# Promless_Power.net
KiCad netlist of a schematic drawn in Altium Designer
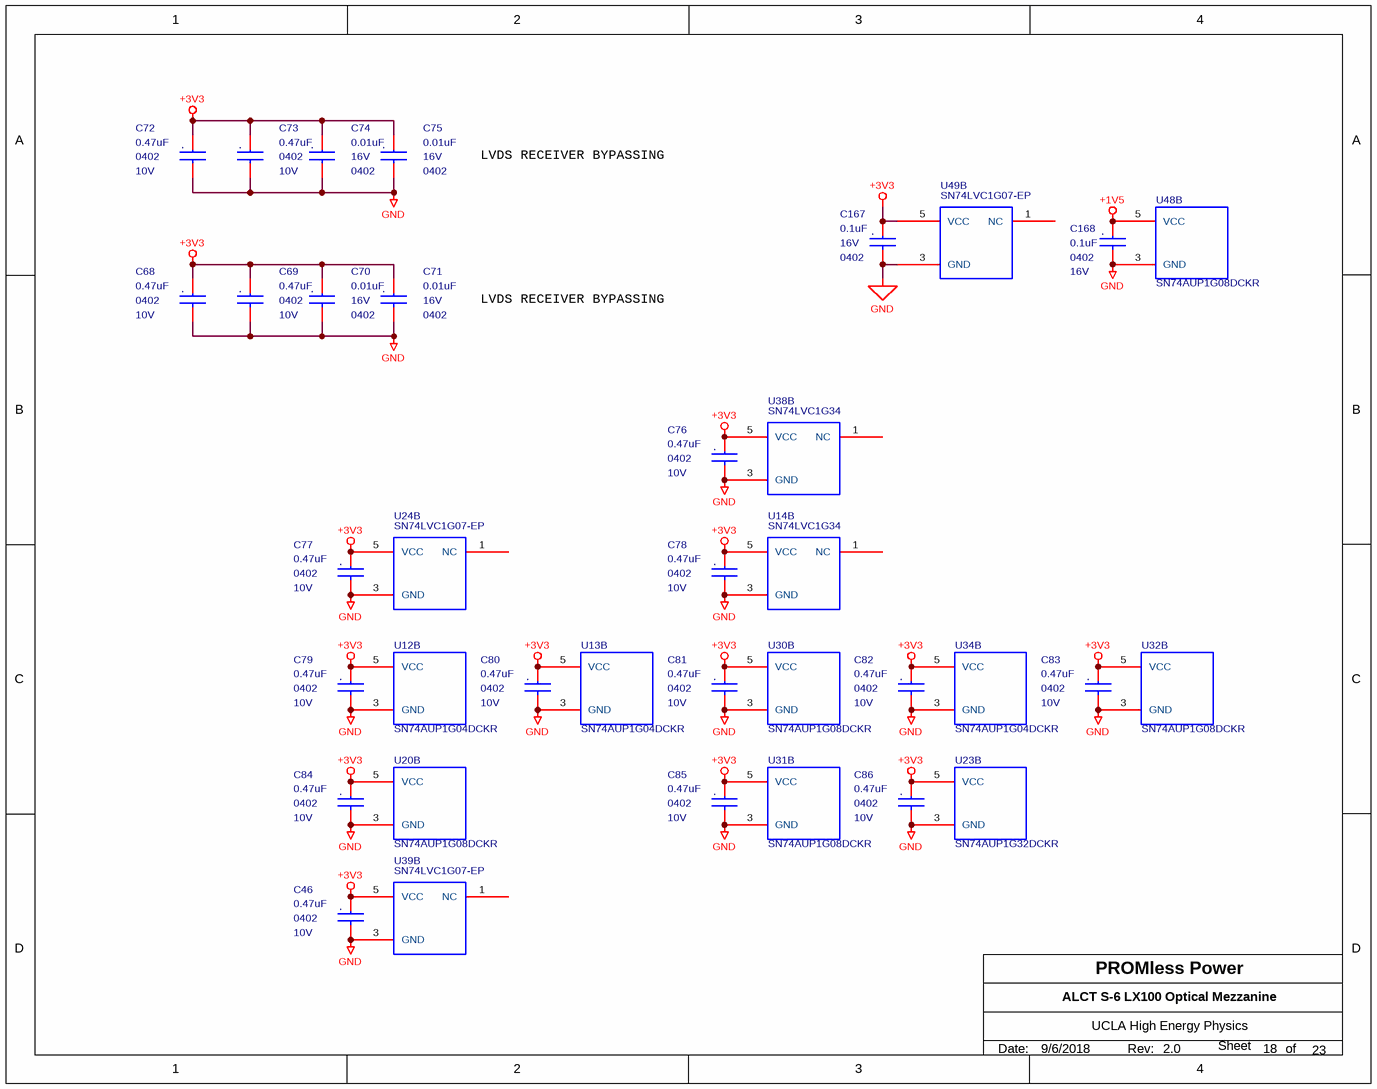
[diagram p0: Promless_Power.SchDoc]

(export (version "E")
  (design (tool "Eeschema 10.0.6"))
  (components
    (comp (ref "C46")
      (value "0.47uF")
      (footprint "MC_S6/SM/C_0402_IPC")
      (description "CAP CER 0.47UF 10V X5R 0402")
      (fields
        (field (name "MANUFACTURER") "Murata Electronics North America")
        (field (name "MANUFACTURER PART NUMBER") "GRM155R61A474KE15D")
        (field (name "VOLTAGE - RATED") "10V")
        (field (name "PACKAGE") "0402")
      )
      (libsource (lib "ALCT_MEZ_SPARTAN6_Library") (part "GRM155R61A474KE15D"))
    )
    (comp (ref "C68")
      (value "0.47uF")
      (footprint "MC_S6/SM/C_0402_IPC")
      (description "CAP CER 0.47UF 10V X5R 0402")
      (fields
        (field (name "MANUFACTURER") "Murata Electronics North America")
        (field (name "MANUFACTURER PART NUMBER") "GRM155R61A474KE15D")
        (field (name "VOLTAGE - RATED") "10V")
        (field (name "PACKAGE") "0402")
      )
      (libsource (lib "ALCT_MEZ_SPARTAN6_Library") (part "GRM155R61A474KE15D"))
    )
    (comp (ref "C69")
      (value "0.47uF")
      (footprint "MC_S6/SM/C_0402_IPC")
      (description "CAP CER 0.47UF 10V X5R 0402")
      (fields
        (field (name "MANUFACTURER") "Murata Electronics North America")
        (field (name "MANUFACTURER PART NUMBER") "GRM155R61A474KE15D")
        (field (name "VOLTAGE - RATED") "10V")
        (field (name "PACKAGE") "0402")
      )
      (libsource (lib "ALCT_MEZ_SPARTAN6_Library") (part "GRM155R61A474KE15D"))
    )
    (comp (ref "C70")
      (value "0.01uF")
      (footprint "MC_S6/SM/C_0402_IPC")
      (description "CAP CER 10nF 16V X7R 0402")
      (fields
        (field (name "MANUFACTURER") "KEMET")
        (field (name "MANUFACTURER PART NUMBER") "C0402C103K4RACTU")
        (field (name "VOLTAGE - RATED") "16V")
        (field (name "PACKAGE") "0402")
      )
      (libsource (lib "ALCT_MEZ_SPARTAN6_Library") (part "C0402C103K4RACTU"))
    )
    (comp (ref "C71")
      (value "0.01uF")
      (footprint "MC_S6/SM/C_0402_IPC")
      (description "CAP CER 10nF 16V X7R 0402")
      (fields
        (field (name "MANUFACTURER") "KEMET")
        (field (name "MANUFACTURER PART NUMBER") "C0402C103K4RACTU")
        (field (name "VOLTAGE - RATED") "16V")
        (field (name "PACKAGE") "0402")
      )
      (libsource (lib "ALCT_MEZ_SPARTAN6_Library") (part "C0402C103K4RACTU"))
    )
    (comp (ref "C72")
      (value "0.47uF")
      (footprint "MC_S6/SM/C_0402_IPC")
      (description "CAP CER 0.47UF 10V X5R 0402")
      (fields
        (field (name "MANUFACTURER") "Murata Electronics North America")
        (field (name "MANUFACTURER PART NUMBER") "GRM155R61A474KE15D")
        (field (name "VOLTAGE - RATED") "10V")
        (field (name "PACKAGE") "0402")
      )
      (libsource (lib "ALCT_MEZ_SPARTAN6_Library") (part "GRM155R61A474KE15D"))
    )
    (comp (ref "C73")
      (value "0.47uF")
      (footprint "MC_S6/SM/C_0402_IPC")
      (description "CAP CER 0.47UF 10V X5R 0402")
      (fields
        (field (name "MANUFACTURER") "Murata Electronics North America")
        (field (name "MANUFACTURER PART NUMBER") "GRM155R61A474KE15D")
        (field (name "VOLTAGE - RATED") "10V")
        (field (name "PACKAGE") "0402")
      )
      (libsource (lib "ALCT_MEZ_SPARTAN6_Library") (part "GRM155R61A474KE15D"))
    )
    (comp (ref "C74")
      (value "0.01uF")
      (footprint "MC_S6/SM/C_0402_IPC")
      (description "CAP CER 10nF 16V X7R 0402")
      (fields
        (field (name "MANUFACTURER") "KEMET")
        (field (name "MANUFACTURER PART NUMBER") "C0402C103K4RACTU")
        (field (name "VOLTAGE - RATED") "16V")
        (field (name "PACKAGE") "0402")
      )
      (libsource (lib "ALCT_MEZ_SPARTAN6_Library") (part "C0402C103K4RACTU"))
    )
    (comp (ref "C75")
      (value "0.01uF")
      (footprint "MC_S6/SM/C_0402_IPC")
      (description "CAP CER 10nF 16V X7R 0402")
      (fields
        (field (name "MANUFACTURER") "KEMET")
        (field (name "MANUFACTURER PART NUMBER") "C0402C103K4RACTU")
        (field (name "VOLTAGE - RATED") "16V")
        (field (name "PACKAGE") "0402")
      )
      (libsource (lib "ALCT_MEZ_SPARTAN6_Library") (part "C0402C103K4RACTU"))
    )
    (comp (ref "C76")
      (value "0.47uF")
      (footprint "MC_S6/SM/C_0402_IPC")
      (description "CAP CER 0.47UF 10V X5R 0402")
      (fields
        (field (name "MANUFACTURER") "Murata Electronics North America")
        (field (name "MANUFACTURER PART NUMBER") "GRM155R61A474KE15D")
        (field (name "VOLTAGE - RATED") "10V")
        (field (name "PACKAGE") "0402")
      )
      (libsource (lib "ALCT_MEZ_SPARTAN6_Library") (part "GRM155R61A474KE15D"))
    )
    (comp (ref "C77")
      (value "0.47uF")
      (footprint "MC_S6/SM/C_0402_IPC")
      (description "CAP CER 0.47UF 10V X5R 0402")
      (fields
        (field (name "MANUFACTURER") "Murata Electronics North America")
        (field (name "MANUFACTURER PART NUMBER") "GRM155R61A474KE15D")
        (field (name "VOLTAGE - RATED") "10V")
        (field (name "PACKAGE") "0402")
      )
      (libsource (lib "ALCT_MEZ_SPARTAN6_Library") (part "GRM155R61A474KE15D"))
    )
    (comp (ref "C78")
      (value "0.47uF")
      (footprint "MC_S6/SM/C_0402_IPC")
      (description "CAP CER 0.47UF 10V X5R 0402")
      (fields
        (field (name "MANUFACTURER") "Murata Electronics North America")
        (field (name "MANUFACTURER PART NUMBER") "GRM155R61A474KE15D")
        (field (name "VOLTAGE - RATED") "10V")
        (field (name "PACKAGE") "0402")
      )
      (libsource (lib "ALCT_MEZ_SPARTAN6_Library") (part "GRM155R61A474KE15D"))
    )
    (comp (ref "C79")
      (value "0.47uF")
      (footprint "MC_S6/SM/C_0402_IPC")
      (description "CAP CER 0.47UF 10V X5R 0402")
      (fields
        (field (name "MANUFACTURER") "Murata Electronics North America")
        (field (name "MANUFACTURER PART NUMBER") "GRM155R61A474KE15D")
        (field (name "VOLTAGE - RATED") "10V")
        (field (name "PACKAGE") "0402")
      )
      (libsource (lib "ALCT_MEZ_SPARTAN6_Library") (part "GRM155R61A474KE15D"))
    )
    (comp (ref "C80")
      (value "0.47uF")
      (footprint "MC_S6/SM/C_0402_IPC")
      (description "CAP CER 0.47UF 10V X5R 0402")
      (fields
        (field (name "MANUFACTURER") "Murata Electronics North America")
        (field (name "MANUFACTURER PART NUMBER") "GRM155R61A474KE15D")
        (field (name "VOLTAGE - RATED") "10V")
        (field (name "PACKAGE") "0402")
      )
      (libsource (lib "ALCT_MEZ_SPARTAN6_Library") (part "GRM155R61A474KE15D"))
    )
    (comp (ref "C81")
      (value "0.47uF")
      (footprint "MC_S6/SM/C_0402_IPC")
      (description "CAP CER 0.47UF 10V X5R 0402")
      (fields
        (field (name "MANUFACTURER") "Murata Electronics North America")
        (field (name "MANUFACTURER PART NUMBER") "GRM155R61A474KE15D")
        (field (name "VOLTAGE - RATED") "10V")
        (field (name "PACKAGE") "0402")
      )
      (libsource (lib "ALCT_MEZ_SPARTAN6_Library") (part "GRM155R61A474KE15D"))
    )
    (comp (ref "C82")
      (value "0.47uF")
      (footprint "MC_S6/SM/C_0402_IPC")
      (description "CAP CER 0.47UF 10V X5R 0402")
      (fields
        (field (name "MANUFACTURER") "Murata Electronics North America")
        (field (name "MANUFACTURER PART NUMBER") "GRM155R61A474KE15D")
        (field (name "VOLTAGE - RATED") "10V")
        (field (name "PACKAGE") "0402")
      )
      (libsource (lib "ALCT_MEZ_SPARTAN6_Library") (part "GRM155R61A474KE15D"))
    )
    (comp (ref "C83")
      (value "0.47uF")
      (footprint "MC_S6/SM/C_0402_IPC")
      (description "CAP CER 0.47UF 10V X5R 0402")
      (fields
        (field (name "MANUFACTURER") "Murata Electronics North America")
        (field (name "MANUFACTURER PART NUMBER") "GRM155R61A474KE15D")
        (field (name "VOLTAGE - RATED") "10V")
        (field (name "PACKAGE") "0402")
      )
      (libsource (lib "ALCT_MEZ_SPARTAN6_Library") (part "GRM155R61A474KE15D"))
    )
    (comp (ref "C84")
      (value "0.47uF")
      (footprint "MC_S6/SM/C_0402_IPC")
      (description "CAP CER 0.47UF 10V X5R 0402")
      (fields
        (field (name "MANUFACTURER") "Murata Electronics North America")
        (field (name "MANUFACTURER PART NUMBER") "GRM155R61A474KE15D")
        (field (name "VOLTAGE - RATED") "10V")
        (field (name "PACKAGE") "0402")
      )
      (libsource (lib "ALCT_MEZ_SPARTAN6_Library") (part "GRM155R61A474KE15D"))
    )
    (comp (ref "C85")
      (value "0.47uF")
      (footprint "MC_S6/SM/C_0402_IPC")
      (description "CAP CER 0.47UF 10V X5R 0402")
      (fields
        (field (name "MANUFACTURER") "Murata Electronics North America")
        (field (name "MANUFACTURER PART NUMBER") "GRM155R61A474KE15D")
        (field (name "VOLTAGE - RATED") "10V")
        (field (name "PACKAGE") "0402")
      )
      (libsource (lib "ALCT_MEZ_SPARTAN6_Library") (part "GRM155R61A474KE15D"))
    )
    (comp (ref "C86")
      (value "0.47uF")
      (footprint "MC_S6/SM/C_0402_IPC")
      (description "CAP CER 0.47UF 10V X5R 0402")
      (fields
        (field (name "MANUFACTURER") "Murata Electronics North America")
        (field (name "MANUFACTURER PART NUMBER") "GRM155R61A474KE15D")
        (field (name "VOLTAGE - RATED") "10V")
        (field (name "PACKAGE") "0402")
      )
      (libsource (lib "ALCT_MEZ_SPARTAN6_Library") (part "GRM155R61A474KE15D"))
    )
    (comp (ref "C167")
      (value "0.1uF")
      (footprint "MC_S6/SM/C_0402_IPC")
      (description "CAP CER 0.1UF 16V X7R 0402")
      (fields
        (field (name "MANUFACTURER") "KEMET")
        (field (name "MANUFACTURER PART NUMBER") "C0402C104K4RACTU")
        (field (name "PACKAGE") "0402")
        (field (name "VOLTAGE - RATED") "16V")
      )
      (libsource (lib "ALCT_MEZ_SPARTAN6_Library") (part "C0402C104K4RACTU"))
    )
    (comp (ref "C168")
      (value "0.1uF")
      (footprint "MC_S6/SM/C_0402_IPC")
      (description "CAP CER 0.1UF 16V X7R 0402")
      (fields
        (field (name "MANUFACTURER") "KEMET")
        (field (name "MANUFACTURER PART NUMBER") "C0402C104K4RACTU")
        (field (name "PACKAGE") "0402")
        (field (name "VOLTAGE - RATED") "16V")
      )
      (libsource (lib "ALCT_MEZ_SPARTAN6_Library") (part "C0402C104K4RACTU"))
    )
    (comp (ref "U12")
      (value "SN74AUP1G04DCKR")
      (footprint "MC_S6/SM/SOT_SC70_DCK5")
      (description "IC INVERTER LP 5TSSOP")
      (fields (field (name "MANUFACTURER") "Texas Instruments"))
      (libsource (lib "ALCT_MEZ_SPARTAN6_Library") (part "SN74AUP1G04DCKR"))
    )
    (comp (ref "U13")
      (value "SN74AUP1G04DCKR")
      (footprint "MC_S6/SM/SOT_SC70_DCK5")
      (description "IC INVERTER LP 5TSSOP")
      (fields (field (name "MANUFACTURER") "Texas Instruments"))
      (libsource (lib "ALCT_MEZ_SPARTAN6_Library") (part "SN74AUP1G04DCKR"))
    )
    (comp (ref "U14")
      (value "SN74LVC1G34")
      (footprint "MC_S6/SM/SOT_553_DRL5")
      (description "IC BUFFER NON-INVERT SOT5")
      (fields
        (field (name "MANUFACTURER") "Texas Instruments")
        (field (name "MANUFACTURER PART NUMBER") "SN74LVC1G34DRLR")
      )
      (libsource (lib "ALCT_MEZ_SPARTAN6_Library") (part "SN74LVC1G34DRLR"))
    )
    (comp (ref "U20")
      (value "SN74AUP1G08DCKR")
      (footprint "MC_S6/SM/SOT_SC70_DCK5")
      (description "IC GATE AND 1CH 2-INP 5-TSSOP")
      (fields
        (field (name "MANUFACTURER") "Texas Instruments")
        (field (name "MANUFACTURER PART NUMBER") "SN74AUP1G08DCKT")
      )
      (libsource (lib "ALCT_MEZ_SPARTAN6_Library") (part "SN74AUP1G08DCKR"))
    )
    (comp (ref "U23")
      (value "SN74AUP1G32DCKR")
      (footprint "MC_S6/SM/SOT_SC70_DCK5")
      (description "IC GATE OR 1CH 2-INP 5-TSSOP")
      (fields
        (field (name "MANUFACTURER") "Texas Instruments")
        (field (name "MANUFACTURER PART NUMBER") "SN74AUP1G32DCKT")
      )
      (libsource (lib "ALCT_MEZ_SPARTAN6_Library") (part "SN74AUP1G32DCKR"))
    )
    (comp (ref "U24")
      (value "SN74LVC1G07-EP")
      (footprint "SOT353-1")
      (description "IC BUFF/DVR NON-INVERT Open Drain SC70-5")
      (fields
        (field (name "MANUFACTURER") "Texas Instruments")
        (field (name "MANUFACTURER PART NUMBER") "SN74LVC1G07MDCKREP")
      )
      (libsource (lib "ALCT_MEZ_SPARTAN6_Library") (part "SN74LVC1G07-EP"))
    )
    (comp (ref "U30")
      (value "SN74AUP1G08DCKR")
      (footprint "MC_S6/SM/SOT_SC70_DCK5")
      (description "IC GATE AND 1CH 2-INP 5-TSSOP")
      (fields
        (field (name "MANUFACTURER") "Texas Instruments")
        (field (name "MANUFACTURER PART NUMBER") "SN74AUP1G08DCKT")
      )
      (libsource (lib "ALCT_MEZ_SPARTAN6_Library") (part "SN74AUP1G08DCKR"))
    )
    (comp (ref "U31")
      (value "SN74AUP1G08DCKR")
      (footprint "MC_S6/SM/SOT_SC70_DCK5")
      (description "IC GATE AND 1CH 2-INP 5-TSSOP")
      (fields
        (field (name "MANUFACTURER") "Texas Instruments")
        (field (name "MANUFACTURER PART NUMBER") "SN74AUP1G08DCKT")
      )
      (libsource (lib "ALCT_MEZ_SPARTAN6_Library") (part "SN74AUP1G08DCKR"))
    )
    (comp (ref "U32")
      (value "SN74AUP1G08DCKR")
      (footprint "MC_S6/SM/SOT_SC70_DCK5")
      (description "IC GATE AND 1CH 2-INP 5-TSSOP")
      (fields
        (field (name "MANUFACTURER") "Texas Instruments")
        (field (name "MANUFACTURER PART NUMBER") "SN74AUP1G08DCKT")
      )
      (libsource (lib "ALCT_MEZ_SPARTAN6_Library") (part "SN74AUP1G08DCKR"))
    )
    (comp (ref "U34")
      (value "SN74AUP1G04DCKR")
      (footprint "MC_S6/SM/SOT_SC70_DCK5")
      (description "IC INVERTER LP 5TSSOP")
      (fields (field (name "MANUFACTURER") "Texas Instruments"))
      (libsource (lib "ALCT_MEZ_SPARTAN6_Library") (part "SN74AUP1G04DCKR"))
    )
    (comp (ref "U38")
      (value "SN74LVC1G34")
      (footprint "MC_S6/SM/SOT_553_DRL5")
      (description "IC BUFFER NON-INVERT SOT5")
      (fields
        (field (name "MANUFACTURER") "Texas Instruments")
        (field (name "MANUFACTURER PART NUMBER") "SN74LVC1G34DRLR")
      )
      (libsource (lib "ALCT_MEZ_SPARTAN6_Library") (part "SN74LVC1G34DRLR"))
    )
    (comp (ref "U39")
      (value "SN74LVC1G07-EP")
      (footprint "SOT353-1")
      (description "IC BUFF/DVR NON-INVERT Open Drain SC70-5")
      (fields
        (field (name "MANUFACTURER") "Texas Instruments")
        (field (name "MANUFACTURER PART NUMBER") "SN74LVC1G07MDCKREP")
      )
      (libsource (lib "ALCT_MEZ_SPARTAN6_Library") (part "SN74LVC1G07-EP"))
    )
    (comp (ref "U48")
      (value "SN74AUP1G08DCKR")
      (footprint "MC_S6/SM/SOT_SC70_DCK5")
      (description "IC GATE AND 1CH 2-INP 5-TSSOP")
      (fields
        (field (name "MANUFACTURER") "Texas Instruments")
        (field (name "MANUFACTURER PART NUMBER") "SN74AUP1G08DCKT")
      )
      (libsource (lib "ALCT_MEZ_SPARTAN6_Library") (part "SN74AUP1G08DCKR"))
    )
    (comp (ref "U49")
      (value "SN74LVC1G07-EP")
      (footprint "SOT353-1")
      (description "IC BUFF/DVR NON-INVERT Open Drain SC70-5")
      (fields
        (field (name "MANUFACTURER") "Texas Instruments")
        (field (name "MANUFACTURER PART NUMBER") "SN74LVC1G07MDCKREP")
      )
      (libsource (lib "ALCT_MEZ_SPARTAN6_Library") (part "SN74LVC1G07-EP"))
    )
  )
  (nets
    (net (code "1") (name "+1V5") (class "Default")
      (node (ref "C168") (pin "1") (pinfunction "1_1") (pintype "passive"))
      (node (ref "U48") (pin "5") (pinfunction "VCC_5") (pintype "power_in"))
    )
    (net (code "2") (name "+3V3") (class "Default")
      (node (ref "C167") (pin "1") (pinfunction "1_1") (pintype "passive"))
      (node (ref "C46") (pin "1") (pinfunction "1_1") (pintype "passive"))
      (node (ref "C68") (pin "1") (pinfunction "1_1") (pintype "passive"))
      (node (ref "C69") (pin "1") (pinfunction "1_1") (pintype "passive"))
      (node (ref "C70") (pin "1") (pinfunction "1_1") (pintype "passive"))
      (node (ref "C71") (pin "1") (pinfunction "1_1") (pintype "passive"))
      (node (ref "C72") (pin "1") (pinfunction "1_1") (pintype "passive"))
      (node (ref "C73") (pin "1") (pinfunction "1_1") (pintype "passive"))
      (node (ref "C74") (pin "1") (pinfunction "1_1") (pintype "passive"))
      (node (ref "C75") (pin "1") (pinfunction "1_1") (pintype "passive"))
      (node (ref "C76") (pin "1") (pinfunction "1_1") (pintype "passive"))
      (node (ref "C77") (pin "1") (pinfunction "1_1") (pintype "passive"))
      (node (ref "C78") (pin "1") (pinfunction "1_1") (pintype "passive"))
      (node (ref "C79") (pin "1") (pinfunction "1_1") (pintype "passive"))
      (node (ref "C80") (pin "1") (pinfunction "1_1") (pintype "passive"))
      (node (ref "C81") (pin "1") (pinfunction "1_1") (pintype "passive"))
      (node (ref "C82") (pin "1") (pinfunction "1_1") (pintype "passive"))
      (node (ref "C83") (pin "1") (pinfunction "1_1") (pintype "passive"))
      (node (ref "C84") (pin "1") (pinfunction "1_1") (pintype "passive"))
      (node (ref "C85") (pin "1") (pinfunction "1_1") (pintype "passive"))
      (node (ref "C86") (pin "1") (pinfunction "1_1") (pintype "passive"))
      (node (ref "U12") (pin "5") (pinfunction "VCC_5") (pintype "power_in"))
      (node (ref "U13") (pin "5") (pinfunction "VCC_5") (pintype "power_in"))
      (node (ref "U14") (pin "5") (pinfunction "VCC_5") (pintype "power_in"))
      (node (ref "U20") (pin "5") (pinfunction "VCC_5") (pintype "power_in"))
      (node (ref "U23") (pin "5") (pinfunction "VCC_5") (pintype "power_in"))
      (node (ref "U24") (pin "5") (pinfunction "VCC_5") (pintype "power_in"))
      (node (ref "U30") (pin "5") (pinfunction "VCC_5") (pintype "power_in"))
      (node (ref "U31") (pin "5") (pinfunction "VCC_5") (pintype "power_in"))
      (node (ref "U32") (pin "5") (pinfunction "VCC_5") (pintype "power_in"))
      (node (ref "U34") (pin "5") (pinfunction "VCC_5") (pintype "power_in"))
      (node (ref "U38") (pin "5") (pinfunction "VCC_5") (pintype "power_in"))
      (node (ref "U39") (pin "5") (pinfunction "VCC_5") (pintype "power_in"))
      (node (ref "U49") (pin "5") (pinfunction "VCC_5") (pintype "power_in"))
    )
    (net (code "3") (name "GND") (class "Default")
      (node (ref "C167") (pin "2") (pinfunction "2_2") (pintype "passive"))
      (node (ref "C168") (pin "2") (pinfunction "2_2") (pintype "passive"))
      (node (ref "C46") (pin "2") (pinfunction "2_2") (pintype "passive"))
      (node (ref "C68") (pin "2") (pinfunction "2_2") (pintype "passive"))
      (node (ref "C69") (pin "2") (pinfunction "2_2") (pintype "passive"))
      (node (ref "C70") (pin "2") (pinfunction "2_2") (pintype "passive"))
      (node (ref "C71") (pin "2") (pinfunction "2_2") (pintype "passive"))
      (node (ref "C72") (pin "2") (pinfunction "2_2") (pintype "passive"))
      (node (ref "C73") (pin "2") (pinfunction "2_2") (pintype "passive"))
      (node (ref "C74") (pin "2") (pinfunction "2_2") (pintype "passive"))
      (node (ref "C75") (pin "2") (pinfunction "2_2") (pintype "passive"))
      (node (ref "C76") (pin "2") (pinfunction "2_2") (pintype "passive"))
      (node (ref "C77") (pin "2") (pinfunction "2_2") (pintype "passive"))
      (node (ref "C78") (pin "2") (pinfunction "2_2") (pintype "passive"))
      (node (ref "C79") (pin "2") (pinfunction "2_2") (pintype "passive"))
      (node (ref "C80") (pin "2") (pinfunction "2_2") (pintype "passive"))
      (node (ref "C81") (pin "2") (pinfunction "2_2") (pintype "passive"))
      (node (ref "C82") (pin "2") (pinfunction "2_2") (pintype "passive"))
      (node (ref "C83") (pin "2") (pinfunction "2_2") (pintype "passive"))
      (node (ref "C84") (pin "2") (pinfunction "2_2") (pintype "passive"))
      (node (ref "C85") (pin "2") (pinfunction "2_2") (pintype "passive"))
      (node (ref "C86") (pin "2") (pinfunction "2_2") (pintype "passive"))
      (node (ref "U12") (pin "3") (pinfunction "GND_3") (pintype "power_in"))
      (node (ref "U13") (pin "3") (pinfunction "GND_3") (pintype "power_in"))
      (node (ref "U14") (pin "3") (pinfunction "GND_3") (pintype "power_in"))
      (node (ref "U20") (pin "3") (pinfunction "GND_3") (pintype "power_in"))
      (node (ref "U23") (pin "3") (pinfunction "GND_3") (pintype "power_in"))
      (node (ref "U24") (pin "3") (pinfunction "GND_3") (pintype "power_in"))
      (node (ref "U30") (pin "3") (pinfunction "GND_3") (pintype "power_in"))
      (node (ref "U31") (pin "3") (pinfunction "GND_3") (pintype "power_in"))
      (node (ref "U32") (pin "3") (pinfunction "GND_3") (pintype "power_in"))
      (node (ref "U34") (pin "3") (pinfunction "GND_3") (pintype "power_in"))
      (node (ref "U38") (pin "3") (pinfunction "GND_3") (pintype "power_in"))
      (node (ref "U39") (pin "3") (pinfunction "GND_3") (pintype "power_in"))
      (node (ref "U48") (pin "3") (pinfunction "GND_3") (pintype "power_in"))
      (node (ref "U49") (pin "3") (pinfunction "GND_3") (pintype "power_in"))
    )
    (net (code "4") (name "unconnected-(U14B-NC-Pad1)") (class "Default")
      (node (ref "U14") (pin "1") (pinfunction "NC_1") (pintype "passive"))
    )
    (net (code "5") (name "unconnected-(U24B-NC-Pad1)") (class "Default")
      (node (ref "U24") (pin "1") (pinfunction "NC_1") (pintype "passive"))
    )
    (net (code "6") (name "unconnected-(U38B-NC-Pad1)") (class "Default")
      (node (ref "U38") (pin "1") (pinfunction "NC_1") (pintype "passive"))
    )
    (net (code "7") (name "unconnected-(U39B-NC-Pad1)") (class "Default")
      (node (ref "U39") (pin "1") (pinfunction "NC_1") (pintype "passive"))
    )
    (net (code "8") (name "unconnected-(U49B-NC-Pad1)") (class "Default")
      (node (ref "U49") (pin "1") (pinfunction "NC_1") (pintype "passive"))
    )
  )
)
